# Relay.net
KiCad netlist of a schematic drawn in Altium Designer
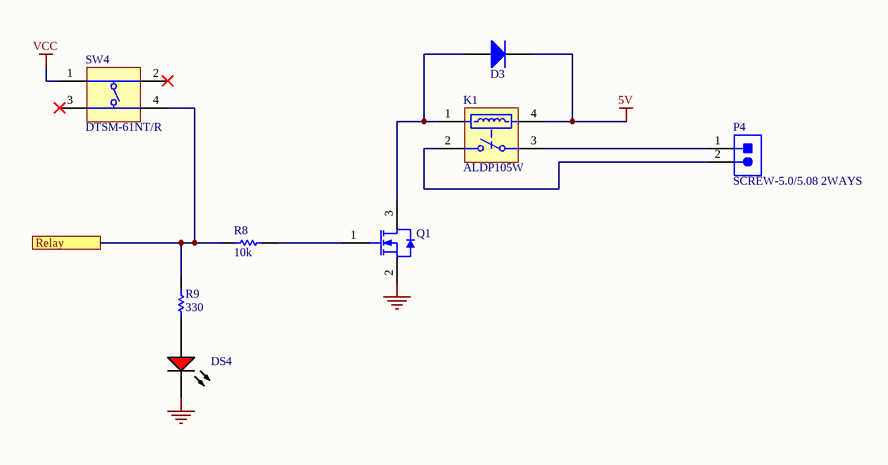
[diagram p0: Relay.SchDoc]

(export (version "E")
  (design (tool "Eeschema 10.0.6"))
  (components
    (comp (ref "D3")
      (value "MMSD4148T3G")
      (footprint "ONSC-SOD123-2-425G-04_V")
      (description "Switching Diode, 100 V, 200 mA, -55 to 150 degC, 2-Pin SOD123 (425), RoHS, Tape and Reel")
      (fields (field (name "MANUFACTURER") "ON Semiconductor"))
      (libsource (lib "Altium Content Vault") (part "ONSC-MMSD4148-SOD123-2"))
    )
    (comp (ref "DS4")
      (value "TLMS1100-GS08")
      (footprint "VISH-TLMX1100_V")
      (description "LED, RED, 2.1 V, -40 to 100 degC, 2-Pin SMD (0603), RoHS, Tape and Reel")
      (fields (field (name "TOLERANCE") "5%"))
      (libsource (lib "Altium Content Vault") (part "LED-RED-AK-2"))
    )
    (comp (ref "K1")
      (value "ALDP105W")
      (footprint "PNSC-LD-P-4-2050x720x1530_V")
      (fields (field (name "MANUFACTURER") "Panasonic"))
      (libsource (lib "Altium Content Vault") (part "PNSC-ALDP105W-LD-P-4-2050x720x1530-4"))
    )
    (comp (ref "P4")
      (value "SCREW-5.0/5.08 2WAYS")
      (footprint "SCREW-5.0-2WAYS_V")
      (description "Socket, Screw Terminal Block, 2 Way, 5.0 mm Pitch, 90 Degree Angle, Through-Hole")
      (fields (field (name "MANUFACTURER") "No Vendor"))
      (libsource (lib "Altium Content Vault") (part "SCREW-2WAYS"))
    )
    (comp (ref "Q1")
      (value "IRLML2502TRPBF")
      (footprint "INTR-SOT-23-3_V")
      (description "N-Channel HEXFET(R) Power MOSFET, 20 V VDS, +/- 12 V VGS, 4.2 A, 3-Pin SOT23, RoHS, Tape and Reel")
      (fields (field (name "MANUFACTURER") "International Rectifier"))
      (libsource (lib "Altium Content Vault") (part "NEMOS-GSD-3"))
    )
    (comp (ref "R8")
      (value "10k")
      (footprint "RESC0805(2012)_L")
      (description "10K2 0.125W 1% 0805 (2012 Metric)  SMD")
      (fields (field (name "TOLERANCE") "1 %") (field (name "POWER") "0.125 W"))
      (libsource (lib "Altium Content Vault") (part "RES"))
    )
    (comp (ref "R9")
      (value "330")
      (footprint "RESC0805(2012)_L")
      (description "10K2 0.125W 1% 0805 (2012 Metric)  SMD")
      (fields (field (name "TOLERANCE") "1 %") (field (name "POWER") "0.125 W"))
      (libsource (lib "Altium Content Vault") (part "RES"))
    )
    (comp (ref "SW4")
      (value "DTSM-61NT/R")
      (footprint "DIPT-DTSM-6_V")
      (description "Switch, SPNO Push Button SMD")
      (fields (field (name "MANUFACTURER") "Diptronics"))
      (libsource (lib "Altium Content Vault") (part "DIPT-DTSM-6"))
    )
  )
  (nets
    (net (code "1") (name "/Relay") (class "Default")
      (node (ref "R8") (pin "2") (pinfunction "2_2") (pintype "passive"))
      (node (ref "R9") (pin "1") (pinfunction "1_1") (pintype "passive"))
      (node (ref "SW4") (pin "4") (pinfunction "T3_4") (pintype "passive"))
    )
    (net (code "2") (name "5V") (class "Default")
      (node (ref "D3") (pin "1") (pinfunction "CATHODE_1") (pintype "passive"))
      (node (ref "K1") (pin "4") (pinfunction "4_4") (pintype "passive"))
    )
    (net (code "3") (name "GND") (class "Default")
      (node (ref "DS4") (pin "2") (pinfunction "K_2") (pintype "passive"))
      (node (ref "Q1") (pin "2") (pinfunction "S_2") (pintype "passive"))
    )
    (net (code "4") (name "Net-(D3-ANODE)") (class "Default")
      (node (ref "D3") (pin "2") (pinfunction "ANODE_2") (pintype "passive"))
      (node (ref "K1") (pin "1") (pinfunction "1_1") (pintype "passive"))
      (node (ref "Q1") (pin "3") (pinfunction "D_3") (pintype "passive"))
    )
    (net (code "5") (name "Net-(DS4-A)") (class "Default")
      (node (ref "DS4") (pin "1") (pinfunction "A_1") (pintype "passive"))
      (node (ref "R9") (pin "2") (pinfunction "2_2") (pintype "passive"))
    )
    (net (code "6") (name "Net-(K1-COM)") (class "Default")
      (node (ref "K1") (pin "3") (pinfunction "COM_3") (pintype "passive"))
      (node (ref "P4") (pin "1") (pinfunction "1_1") (pintype "passive"))
    )
    (net (code "7") (name "Net-(K1-NO)") (class "Default")
      (node (ref "K1") (pin "2") (pinfunction "NO_2") (pintype "passive"))
      (node (ref "P4") (pin "2") (pinfunction "2_2") (pintype "passive"))
    )
    (net (code "8") (name "Net-(Q1-G)") (class "Default")
      (node (ref "Q1") (pin "1") (pinfunction "G_1") (pintype "passive"))
      (node (ref "R8") (pin "1") (pinfunction "1_1") (pintype "passive"))
    )
    (net (code "9") (name "VCC") (class "Default")
      (node (ref "SW4") (pin "1") (pinfunction "T1_1") (pintype "passive"))
    )
    (net (code "10") (name "unconnected-(SW4-T2-Pad2)") (class "Default")
      (node (ref "SW4") (pin "2") (pinfunction "T2_2") (pintype "passive+no_connect"))
    )
    (net (code "11") (name "unconnected-(SW4-T3-Pad3)") (class "Default")
      (node (ref "SW4") (pin "3") (pinfunction "T3_3") (pintype "passive+no_connect"))
    )
  )
)
